# esp01-shield.net
KiCad netlist of a schematic drawn in EAGLE
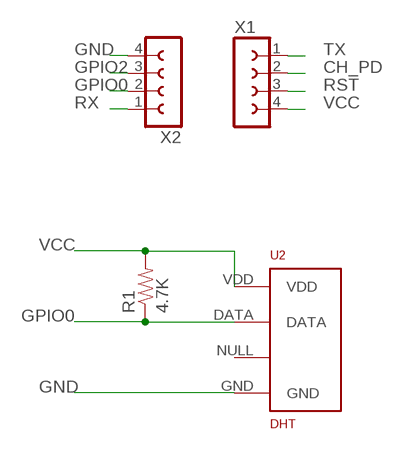
[diagram p0: schematic, sheet 1]

(export (version "E")
  (design (tool "Eeschema 10.0.6"))
  (components
    (comp (ref "R1")
      (value "4.7K")
      (footprint "eagle-import:1_6W-RES")
      (libsource (lib "eagle-import") (part "RESISTORPTH-1/6W"))
    )
    (comp (ref "U2")
      (value "DHT")
      (footprint "eagle-import:RHT03_DHT-22")
      (libsource (lib "eagle-import") (part "RHT03_DHT-22_AM2302"))
    )
    (comp (ref "X1")
      (value "SPB4")
      (footprint "eagle-import:SPB4")
      (libsource (lib "eagle-import") (part "SPB4"))
    )
    (comp (ref "X2")
      (value "SPB4")
      (footprint "eagle-import:SPB4")
      (libsource (lib "eagle-import") (part "SPB4"))
    )
  )
  (nets
    (net (code "1") (name "/CH_PD") (class "Default")
      (node (ref "X1") (pin "2") (pinfunction "2_2") (pintype "passive"))
    )
    (net (code "2") (name "/GND") (class "Default")
      (node (ref "U2") (pin "GND") (pinfunction "GND_GND") (pintype "power_in"))
      (node (ref "X2") (pin "4") (pinfunction "4_4") (pintype "passive"))
    )
    (net (code "3") (name "/GPIO0") (class "Default")
      (node (ref "R1") (pin "1") (pinfunction "1_1") (pintype "passive"))
      (node (ref "U2") (pin "DATA") (pinfunction "DATA_DATA") (pintype "bidirectional"))
      (node (ref "X2") (pin "2") (pinfunction "2_2") (pintype "passive"))
    )
    (net (code "4") (name "/GPIO2") (class "Default")
      (node (ref "X2") (pin "3") (pinfunction "3_3") (pintype "passive"))
    )
    (net (code "5") (name "/RST") (class "Default")
      (node (ref "X1") (pin "3") (pinfunction "3_3") (pintype "passive"))
    )
    (net (code "6") (name "/RX") (class "Default")
      (node (ref "X2") (pin "1") (pinfunction "1_1") (pintype "passive"))
    )
    (net (code "7") (name "/TX") (class "Default")
      (node (ref "X1") (pin "1") (pinfunction "1_1") (pintype "passive"))
    )
    (net (code "8") (name "/VCC") (class "Default")
      (node (ref "R1") (pin "2") (pinfunction "2_2") (pintype "passive"))
      (node (ref "U2") (pin "VDD") (pinfunction "VDD_VDD") (pintype "power_in"))
      (node (ref "X1") (pin "4") (pinfunction "4_4") (pintype "passive"))
    )
    (net (code "9") (name "unconnected-(U2-PadNULL)") (class "Default")
      (node (ref "U2") (pin "NULL") (pinfunction "NULL_NULL") (pintype "no_connect"))
    )
  )
)
